# HzMF_Odrive_MCU.net
KiCad netlist of a schematic drawn in Altium Designer
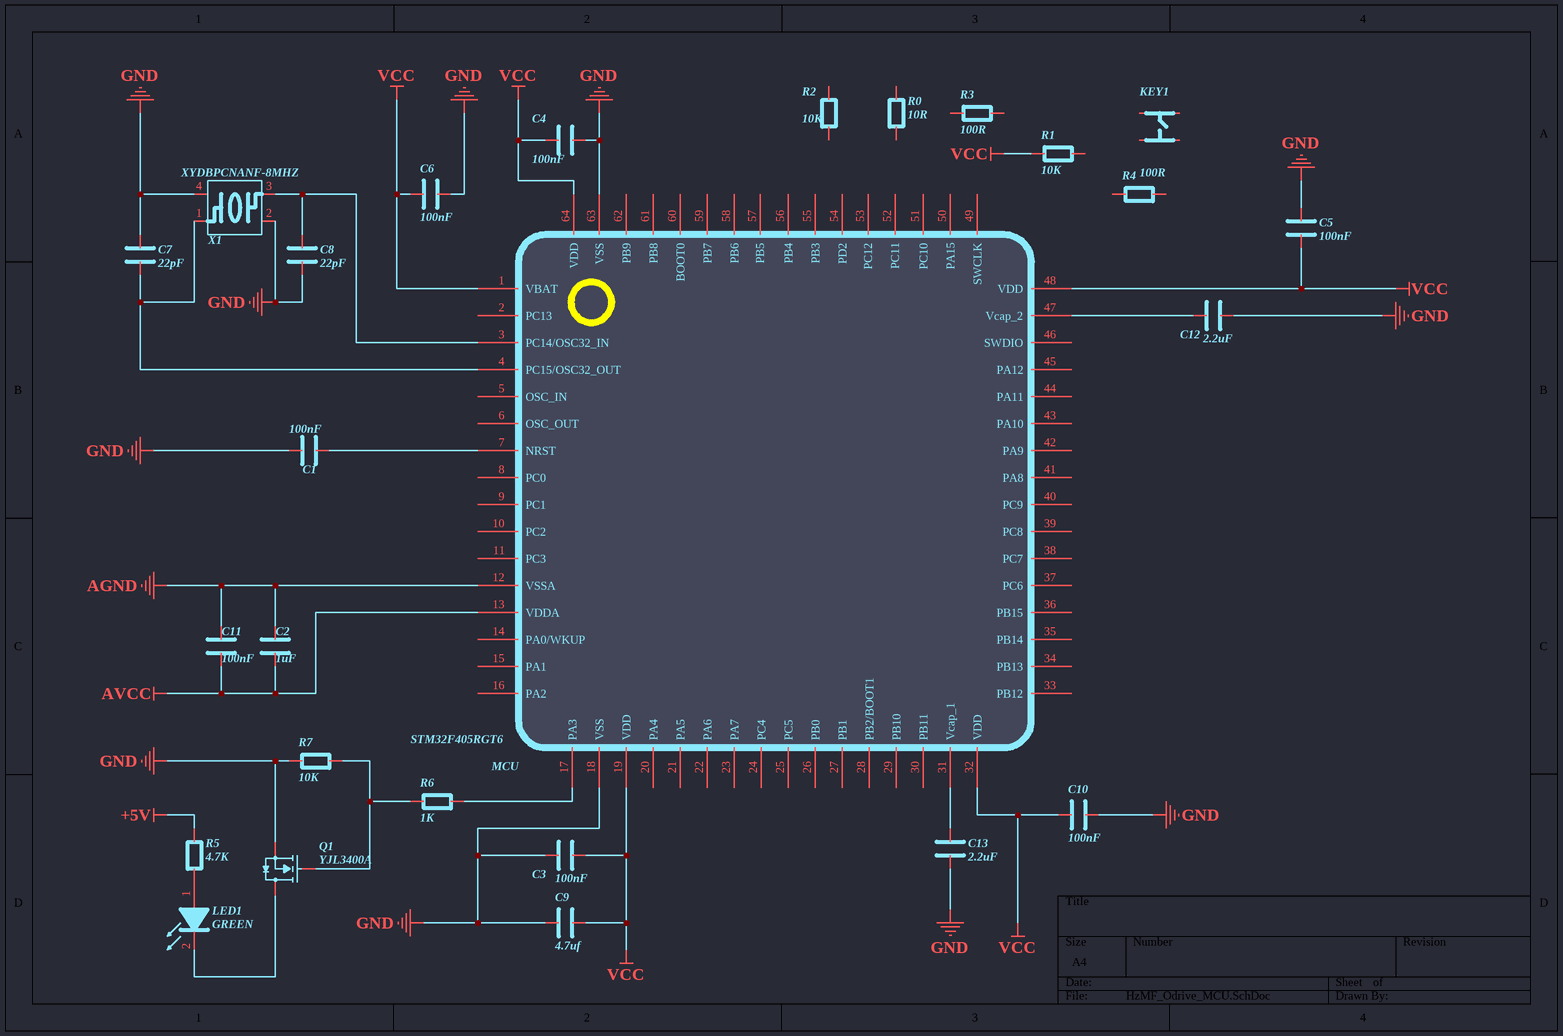
[diagram p0: HzMF_Odrive_MCU.SchDoc]

(export (version "E")
  (design (tool "Eeschema 10.0.6"))
  (components
    (comp (ref "C1")
      (value "100nF")
      (footprint "CAP_0603")
      (libsource (lib "HZMF_Private_Library") (part "C"))
    )
    (comp (ref "C2")
      (value "1uF")
      (footprint "CAP_0603")
      (description "电容")
      (libsource (lib "HZMF_Private_Library") (part "C"))
    )
    (comp (ref "C3")
      (value "100nF")
      (footprint "CAP_0603")
      (description "电容")
      (libsource (lib "HZMF_Private_Library") (part "C"))
    )
    (comp (ref "C4")
      (value "100nF")
      (footprint "CAP_0603")
      (description "电容")
      (libsource (lib "HZMF_Private_Library") (part "C"))
    )
    (comp (ref "C5")
      (value "100nF")
      (footprint "CAP_0603")
      (description "电容")
      (libsource (lib "HZMF_Private_Library") (part "C"))
    )
    (comp (ref "C6")
      (value "100nF")
      (footprint "CAP_0603")
      (description "电容")
      (libsource (lib "HZMF_Private_Library") (part "C"))
    )
    (comp (ref "C7")
      (value "22pF")
      (footprint "CAP_0603")
      (description "电容")
      (libsource (lib "HZMF_Private_Library") (part "C"))
    )
    (comp (ref "C8")
      (value "22pF")
      (footprint "CAP_0603")
      (description "电容")
      (libsource (lib "HZMF_Private_Library") (part "C"))
    )
    (comp (ref "C9")
      (value "4.7uf")
      (footprint "CAP_0603")
      (description "电容")
      (libsource (lib "HZMF_Private_Library") (part "C"))
    )
    (comp (ref "C10")
      (value "100nF")
      (footprint "CAP_0603")
      (description "电容")
      (libsource (lib "HZMF_Private_Library") (part "C"))
    )
    (comp (ref "C11")
      (value "100nF")
      (footprint "CAP_0603")
      (description "电容")
      (libsource (lib "HZMF_Private_Library") (part "C"))
    )
    (comp (ref "C12")
      (value "2.2uF")
      (footprint "CAP_0603")
      (description "电容")
      (libsource (lib "HZMF_Private_Library") (part "C"))
    )
    (comp (ref "C13")
      (value "2.2uF")
      (footprint "CAP_0603")
      (description "电容")
      (libsource (lib "HZMF_Private_Library") (part "C"))
    )
    (comp (ref "KEY1")
      (value "K1")
      (footprint "KEY-SMD_4P-L6.0-W6.0-P4.50-LS10.0")
      (description "Button")
      (libsource (lib "HZMF_Private_Library") (part "Button_4P"))
    )
    (comp (ref "LED1")
      (value "GREEN")
      (footprint "LED_green")
      (description "LED灯")
      (libsource (lib "HZMF_Private_Library") (part "LED"))
    )
    (comp (ref "MCU")
      (value "STM32F405RGT6")
      (footprint "LQFP_64")
      (description "STM32F4")
      (libsource (lib "HZMF_Private_Library") (part "STM32F405RGT6"))
    )
    (comp (ref "Q1")
      (value "YJL3400A")
      (footprint "SOT23_3")
      (description "N_MOS")
      (libsource (lib "HZMF_Private_Library") (part "MOSFET_N"))
    )
    (comp (ref "R0")
      (value "10R")
      (footprint "RES_0603")
      (description "电阻")
      (libsource (lib "HZMF_Private_Library") (part "R"))
    )
    (comp (ref "R1") (value "10K") (footprint "RES_0603") (libsource (lib "HZMF_Private_Library") (part "R")))
    (comp (ref "R2")
      (value "10K")
      (footprint "RES_0603")
      (description "电阻")
      (libsource (lib "HZMF_Private_Library") (part "R"))
    )
    (comp (ref "R3")
      (value "100R")
      (footprint "RES_0603")
      (description "电阻")
      (libsource (lib "HZMF_Private_Library") (part "R"))
    )
    (comp (ref "R4")
      (value "100R")
      (footprint "RES_0603")
      (description "电阻")
      (libsource (lib "HZMF_Private_Library") (part "R"))
    )
    (comp (ref "R5")
      (value "4.7K")
      (footprint "RES_0603")
      (description "电阻")
      (libsource (lib "HZMF_Private_Library") (part "R"))
    )
    (comp (ref "R6")
      (value "1K")
      (footprint "RES_0603")
      (description "电阻")
      (libsource (lib "HZMF_Private_Library") (part "R"))
    )
    (comp (ref "R7")
      (value "10K")
      (footprint "RES_0603")
      (description "电阻")
      (libsource (lib "HZMF_Private_Library") (part "R"))
    )
    (comp (ref "X1")
      (value "XYDBPCNANF-8MHZ")
      (footprint "CARSTAL_4P_2520")
      (description "四脚无源晶振")
      (fields
        (field (name "MANUFACTURER") "TAITIEN(泰艺电子)")
        (field (name "MANUFACTURER PART") "XYDBPCNANF-12MHZ")
      )
      (libsource (lib "HZMF_Private_Library") (part "Crystal_4P"))
    )
  )
  (nets
    (net (code "1") (name "+5V") (class "Default")
      (node (ref "R5") (pin "1") (pinfunction "1_1") (pintype "passive"))
    )
    (net (code "2") (name "AGND") (class "Default")
      (node (ref "C11") (pin "1") (pinfunction "1_1") (pintype "passive"))
      (node (ref "C2") (pin "1") (pinfunction "1_1") (pintype "passive"))
      (node (ref "MCU") (pin "12") (pinfunction "VSSA_12") (pintype "passive"))
    )
    (net (code "3") (name "AVCC") (class "Default")
      (node (ref "C11") (pin "2") (pinfunction "2_2") (pintype "passive"))
      (node (ref "C2") (pin "2") (pinfunction "2_2") (pintype "passive"))
      (node (ref "MCU") (pin "13") (pinfunction "VDDA_13") (pintype "passive"))
    )
    (net (code "4") (name "GND") (class "Default")
      (node (ref "C1") (pin "2") (pinfunction "2_2") (pintype "passive"))
      (node (ref "C10") (pin "1") (pinfunction "1_1") (pintype "passive"))
      (node (ref "C12") (pin "2") (pinfunction "2_2") (pintype "passive"))
      (node (ref "C13") (pin "2") (pinfunction "2_2") (pintype "passive"))
      (node (ref "C3") (pin "1") (pinfunction "1_1") (pintype "passive"))
      (node (ref "C4") (pin "2") (pinfunction "2_2") (pintype "passive"))
      (node (ref "C5") (pin "1") (pinfunction "1_1") (pintype "passive"))
      (node (ref "C6") (pin "1") (pinfunction "1_1") (pintype "passive"))
      (node (ref "C7") (pin "1") (pinfunction "1_1") (pintype "passive"))
      (node (ref "C8") (pin "2") (pinfunction "2_2") (pintype "passive"))
      (node (ref "C9") (pin "1") (pinfunction "1_1") (pintype "passive"))
      (node (ref "MCU") (pin "18") (pinfunction "VSS_18") (pintype "passive"))
      (node (ref "MCU") (pin "63") (pinfunction "VSS_63") (pintype "passive"))
      (node (ref "Q1") (pin "2") (pinfunction "S_2") (pintype "passive"))
      (node (ref "R7") (pin "1") (pinfunction "1_1") (pintype "passive"))
      (node (ref "X1") (pin "2") (pinfunction "GND_2") (pintype "passive"))
      (node (ref "X1") (pin "4") (pinfunction "GND_4") (pintype "passive"))
    )
    (net (code "5") (name "Net-(LED1-+)") (class "Default")
      (node (ref "LED1") (pin "1") (pinfunction "+_1") (pintype "passive"))
      (node (ref "R5") (pin "2") (pinfunction "2_2") (pintype "passive"))
    )
    (net (code "6") (name "Net-(LED1--)") (class "Default")
      (node (ref "LED1") (pin "2") (pinfunction "-_2") (pintype "passive"))
      (node (ref "Q1") (pin "3") (pinfunction "D_3") (pintype "passive"))
    )
    (net (code "7") (name "Net-(MCU-NRST)") (class "Default")
      (node (ref "C1") (pin "1") (pinfunction "1_1") (pintype "passive"))
      (node (ref "MCU") (pin "7") (pinfunction "NRST_7") (pintype "passive"))
    )
    (net (code "8") (name "Net-(MCU-PA3)") (class "Default")
      (node (ref "MCU") (pin "17") (pinfunction "PA3_17") (pintype "passive"))
      (node (ref "R6") (pin "2") (pinfunction "2_2") (pintype "passive"))
    )
    (net (code "9") (name "Net-(MCU-PC14{slash}OSC32_IN)") (class "Default")
      (node (ref "C8") (pin "1") (pinfunction "1_1") (pintype "passive"))
      (node (ref "MCU") (pin "3") (pinfunction "PC14/OSC32_IN_3") (pintype "passive"))
      (node (ref "X1") (pin "3") (pinfunction "3_3") (pintype "passive"))
    )
    (net (code "10") (name "Net-(MCU-PC15{slash}OSC32_OUT)") (class "Default")
      (node (ref "C7") (pin "2") (pinfunction "2_2") (pintype "passive"))
      (node (ref "MCU") (pin "4") (pinfunction "PC15/OSC32_OUT_4") (pintype "passive"))
      (node (ref "X1") (pin "1") (pinfunction "1_1") (pintype "passive"))
    )
    (net (code "11") (name "Net-(MCU-Vcap_1)") (class "Default")
      (node (ref "C13") (pin "1") (pinfunction "1_1") (pintype "passive"))
      (node (ref "MCU") (pin "31") (pinfunction "Vcap_1_31") (pintype "passive"))
    )
    (net (code "12") (name "Net-(MCU-Vcap_2)") (class "Default")
      (node (ref "C12") (pin "1") (pinfunction "1_1") (pintype "passive"))
      (node (ref "MCU") (pin "47") (pinfunction "Vcap_2_47") (pintype "passive"))
    )
    (net (code "13") (name "Net-(Q1-G)") (class "Default")
      (node (ref "Q1") (pin "1") (pinfunction "G_1") (pintype "passive"))
      (node (ref "R6") (pin "1") (pinfunction "1_1") (pintype "passive"))
      (node (ref "R7") (pin "2") (pinfunction "2_2") (pintype "passive"))
    )
    (net (code "14") (name "VCC") (class "Default")
      (node (ref "C10") (pin "2") (pinfunction "2_2") (pintype "passive"))
      (node (ref "C3") (pin "2") (pinfunction "2_2") (pintype "passive"))
      (node (ref "C4") (pin "1") (pinfunction "1_1") (pintype "passive"))
      (node (ref "C5") (pin "2") (pinfunction "2_2") (pintype "passive"))
      (node (ref "C6") (pin "2") (pinfunction "2_2") (pintype "passive"))
      (node (ref "C9") (pin "2") (pinfunction "2_2") (pintype "passive"))
      (node (ref "MCU") (pin "1") (pinfunction "VBAT_1") (pintype "passive"))
      (node (ref "MCU") (pin "19") (pinfunction "VDD_19") (pintype "passive"))
      (node (ref "MCU") (pin "32") (pinfunction "VDD_32") (pintype "passive"))
      (node (ref "MCU") (pin "48") (pinfunction "VDD_48") (pintype "passive"))
      (node (ref "MCU") (pin "64") (pinfunction "VDD_64") (pintype "passive"))
      (node (ref "R1") (pin "2") (pinfunction "2_2") (pintype "passive"))
    )
    (net (code "15") (name "unconnected-(KEY1-Pad1)") (class "Default")
      (node (ref "KEY1") (pin "1") (pinfunction "1_1") (pintype "passive"))
    )
    (net (code "16") (name "unconnected-(KEY1-Pad2)") (class "Default")
      (node (ref "KEY1") (pin "2") (pinfunction "2_2") (pintype "passive"))
    )
    (net (code "17") (name "unconnected-(KEY1-Pad3)") (class "Default")
      (node (ref "KEY1") (pin "3") (pinfunction "3_3") (pintype "passive"))
    )
    (net (code "18") (name "unconnected-(KEY1-Pad4)") (class "Default")
      (node (ref "KEY1") (pin "4") (pinfunction "4_4") (pintype "passive"))
    )
    (net (code "19") (name "unconnected-(MCU-BOOT0-Pad60)") (class "Default")
      (node (ref "MCU") (pin "60") (pinfunction "BOOT0_60") (pintype "passive"))
    )
    (net (code "20") (name "unconnected-(MCU-OSC_IN-Pad5)") (class "Default")
      (node (ref "MCU") (pin "5") (pinfunction "OSC_IN_5") (pintype "passive"))
    )
    (net (code "21") (name "unconnected-(MCU-OSC_OUT-Pad6)") (class "Default")
      (node (ref "MCU") (pin "6") (pinfunction "OSC_OUT_6") (pintype "passive"))
    )
    (net (code "22") (name "unconnected-(MCU-PA0{slash}WKUP-Pad14)") (class "Default")
      (node (ref "MCU") (pin "14") (pinfunction "PA0/WKUP_14") (pintype "passive"))
    )
    (net (code "23") (name "unconnected-(MCU-PA1-Pad15)") (class "Default")
      (node (ref "MCU") (pin "15") (pinfunction "PA1_15") (pintype "passive"))
    )
    (net (code "24") (name "unconnected-(MCU-PA2-Pad16)") (class "Default")
      (node (ref "MCU") (pin "16") (pinfunction "PA2_16") (pintype "passive"))
    )
    (net (code "25") (name "unconnected-(MCU-PA4-Pad20)") (class "Default")
      (node (ref "MCU") (pin "20") (pinfunction "PA4_20") (pintype "passive"))
    )
    (net (code "26") (name "unconnected-(MCU-PA5-Pad21)") (class "Default")
      (node (ref "MCU") (pin "21") (pinfunction "PA5_21") (pintype "passive"))
    )
    (net (code "27") (name "unconnected-(MCU-PA6-Pad22)") (class "Default")
      (node (ref "MCU") (pin "22") (pinfunction "PA6_22") (pintype "passive"))
    )
    (net (code "28") (name "unconnected-(MCU-PA7-Pad23)") (class "Default")
      (node (ref "MCU") (pin "23") (pinfunction "PA7_23") (pintype "passive"))
    )
    (net (code "29") (name "unconnected-(MCU-PA8-Pad41)") (class "Default")
      (node (ref "MCU") (pin "41") (pinfunction "PA8_41") (pintype "passive"))
    )
    (net (code "30") (name "unconnected-(MCU-PA9-Pad42)") (class "Default")
      (node (ref "MCU") (pin "42") (pinfunction "PA9_42") (pintype "passive"))
    )
    (net (code "31") (name "unconnected-(MCU-PA10-Pad43)") (class "Default")
      (node (ref "MCU") (pin "43") (pinfunction "PA10_43") (pintype "passive"))
    )
    (net (code "32") (name "unconnected-(MCU-PA11-Pad44)") (class "Default")
      (node (ref "MCU") (pin "44") (pinfunction "PA11_44") (pintype "passive"))
    )
    (net (code "33") (name "unconnected-(MCU-PA12-Pad45)") (class "Default")
      (node (ref "MCU") (pin "45") (pinfunction "PA12_45") (pintype "passive"))
    )
    (net (code "34") (name "unconnected-(MCU-PA15-Pad50)") (class "Default")
      (node (ref "MCU") (pin "50") (pinfunction "PA15_50") (pintype "passive"))
    )
    (net (code "35") (name "unconnected-(MCU-PB0-Pad26)") (class "Default")
      (node (ref "MCU") (pin "26") (pinfunction "PB0_26") (pintype "passive"))
    )
    (net (code "36") (name "unconnected-(MCU-PB1-Pad27)") (class "Default")
      (node (ref "MCU") (pin "27") (pinfunction "PB1_27") (pintype "passive"))
    )
    (net (code "37") (name "unconnected-(MCU-PB2{slash}BOOT1-Pad28)") (class "Default")
      (node (ref "MCU") (pin "28") (pinfunction "PB2/BOOT1_28") (pintype "passive"))
    )
    (net (code "38") (name "unconnected-(MCU-PB3-Pad55)") (class "Default")
      (node (ref "MCU") (pin "55") (pinfunction "PB3_55") (pintype "passive"))
    )
    (net (code "39") (name "unconnected-(MCU-PB4-Pad56)") (class "Default")
      (node (ref "MCU") (pin "56") (pinfunction "PB4_56") (pintype "passive"))
    )
    (net (code "40") (name "unconnected-(MCU-PB5-Pad57)") (class "Default")
      (node (ref "MCU") (pin "57") (pinfunction "PB5_57") (pintype "passive"))
    )
    (net (code "41") (name "unconnected-(MCU-PB6-Pad58)") (class "Default")
      (node (ref "MCU") (pin "58") (pinfunction "PB6_58") (pintype "passive"))
    )
    (net (code "42") (name "unconnected-(MCU-PB7-Pad59)") (class "Default")
      (node (ref "MCU") (pin "59") (pinfunction "PB7_59") (pintype "passive"))
    )
    (net (code "43") (name "unconnected-(MCU-PB8-Pad61)") (class "Default")
      (node (ref "MCU") (pin "61") (pinfunction "PB8_61") (pintype "passive"))
    )
    (net (code "44") (name "unconnected-(MCU-PB9-Pad62)") (class "Default")
      (node (ref "MCU") (pin "62") (pinfunction "PB9_62") (pintype "passive"))
    )
    (net (code "45") (name "unconnected-(MCU-PB10-Pad29)") (class "Default")
      (node (ref "MCU") (pin "29") (pinfunction "PB10_29") (pintype "passive"))
    )
    (net (code "46") (name "unconnected-(MCU-PB11-Pad30)") (class "Default")
      (node (ref "MCU") (pin "30") (pinfunction "PB11_30") (pintype "passive"))
    )
    (net (code "47") (name "unconnected-(MCU-PB12-Pad33)") (class "Default")
      (node (ref "MCU") (pin "33") (pinfunction "PB12_33") (pintype "passive"))
    )
    (net (code "48") (name "unconnected-(MCU-PB13-Pad34)") (class "Default")
      (node (ref "MCU") (pin "34") (pinfunction "PB13_34") (pintype "passive"))
    )
    (net (code "49") (name "unconnected-(MCU-PB14-Pad35)") (class "Default")
      (node (ref "MCU") (pin "35") (pinfunction "PB14_35") (pintype "passive"))
    )
    (net (code "50") (name "unconnected-(MCU-PB15-Pad36)") (class "Default")
      (node (ref "MCU") (pin "36") (pinfunction "PB15_36") (pintype "passive"))
    )
    (net (code "51") (name "unconnected-(MCU-PC0-Pad8)") (class "Default")
      (node (ref "MCU") (pin "8") (pinfunction "PC0_8") (pintype "passive"))
    )
    (net (code "52") (name "unconnected-(MCU-PC1-Pad9)") (class "Default")
      (node (ref "MCU") (pin "9") (pinfunction "PC1_9") (pintype "passive"))
    )
    (net (code "53") (name "unconnected-(MCU-PC2-Pad10)") (class "Default")
      (node (ref "MCU") (pin "10") (pinfunction "PC2_10") (pintype "passive"))
    )
    (net (code "54") (name "unconnected-(MCU-PC3-Pad11)") (class "Default")
      (node (ref "MCU") (pin "11") (pinfunction "PC3_11") (pintype "passive"))
    )
    (net (code "55") (name "unconnected-(MCU-PC4-Pad24)") (class "Default")
      (node (ref "MCU") (pin "24") (pinfunction "PC4_24") (pintype "passive"))
    )
    (net (code "56") (name "unconnected-(MCU-PC5-Pad25)") (class "Default")
      (node (ref "MCU") (pin "25") (pinfunction "PC5_25") (pintype "passive"))
    )
    (net (code "57") (name "unconnected-(MCU-PC6-Pad37)") (class "Default")
      (node (ref "MCU") (pin "37") (pinfunction "PC6_37") (pintype "passive"))
    )
    (net (code "58") (name "unconnected-(MCU-PC7-Pad38)") (class "Default")
      (node (ref "MCU") (pin "38") (pinfunction "PC7_38") (pintype "passive"))
    )
    (net (code "59") (name "unconnected-(MCU-PC8-Pad39)") (class "Default")
      (node (ref "MCU") (pin "39") (pinfunction "PC8_39") (pintype "passive"))
    )
    (net (code "60") (name "unconnected-(MCU-PC9-Pad40)") (class "Default")
      (node (ref "MCU") (pin "40") (pinfunction "PC9_40") (pintype "passive"))
    )
    (net (code "61") (name "unconnected-(MCU-PC10-Pad51)") (class "Default")
      (node (ref "MCU") (pin "51") (pinfunction "PC10_51") (pintype "passive"))
    )
    (net (code "62") (name "unconnected-(MCU-PC11-Pad52)") (class "Default")
      (node (ref "MCU") (pin "52") (pinfunction "PC11_52") (pintype "passive"))
    )
    (net (code "63") (name "unconnected-(MCU-PC12-Pad53)") (class "Default")
      (node (ref "MCU") (pin "53") (pinfunction "PC12_53") (pintype "passive"))
    )
    (net (code "64") (name "unconnected-(MCU-PC13-Pad2)") (class "Default")
      (node (ref "MCU") (pin "2") (pinfunction "PC13_2") (pintype "passive"))
    )
    (net (code "65") (name "unconnected-(MCU-PD2-Pad54)") (class "Default")
      (node (ref "MCU") (pin "54") (pinfunction "PD2_54") (pintype "passive"))
    )
    (net (code "66") (name "unconnected-(MCU-SWCLK-Pad49)") (class "Default")
      (node (ref "MCU") (pin "49") (pinfunction "SWCLK_49") (pintype "passive"))
    )
    (net (code "67") (name "unconnected-(MCU-SWDIO-Pad46)") (class "Default")
      (node (ref "MCU") (pin "46") (pinfunction "SWDIO_46") (pintype "passive"))
    )
    (net (code "68") (name "unconnected-(R0-Pad1)") (class "Default")
      (node (ref "R0") (pin "1") (pinfunction "1_1") (pintype "passive"))
    )
    (net (code "69") (name "unconnected-(R0-Pad2)") (class "Default")
      (node (ref "R0") (pin "2") (pinfunction "2_2") (pintype "passive"))
    )
    (net (code "70") (name "unconnected-(R1-Pad1)") (class "Default")
      (node (ref "R1") (pin "1") (pinfunction "1_1") (pintype "passive"))
    )
    (net (code "71") (name "unconnected-(R2-Pad1)") (class "Default")
      (node (ref "R2") (pin "1") (pinfunction "1_1") (pintype "passive"))
    )
    (net (code "72") (name "unconnected-(R2-Pad2)") (class "Default")
      (node (ref "R2") (pin "2") (pinfunction "2_2") (pintype "passive"))
    )
    (net (code "73") (name "unconnected-(R3-Pad1)") (class "Default")
      (node (ref "R3") (pin "1") (pinfunction "1_1") (pintype "passive"))
    )
    (net (code "74") (name "unconnected-(R3-Pad2)") (class "Default")
      (node (ref "R3") (pin "2") (pinfunction "2_2") (pintype "passive"))
    )
    (net (code "75") (name "unconnected-(R4-Pad1)") (class "Default")
      (node (ref "R4") (pin "1") (pinfunction "1_1") (pintype "passive"))
    )
    (net (code "76") (name "unconnected-(R4-Pad2)") (class "Default")
      (node (ref "R4") (pin "2") (pinfunction "2_2") (pintype "passive"))
    )
  )
)
